# board.net
KiCad netlist of a schematic drawn in EAGLE
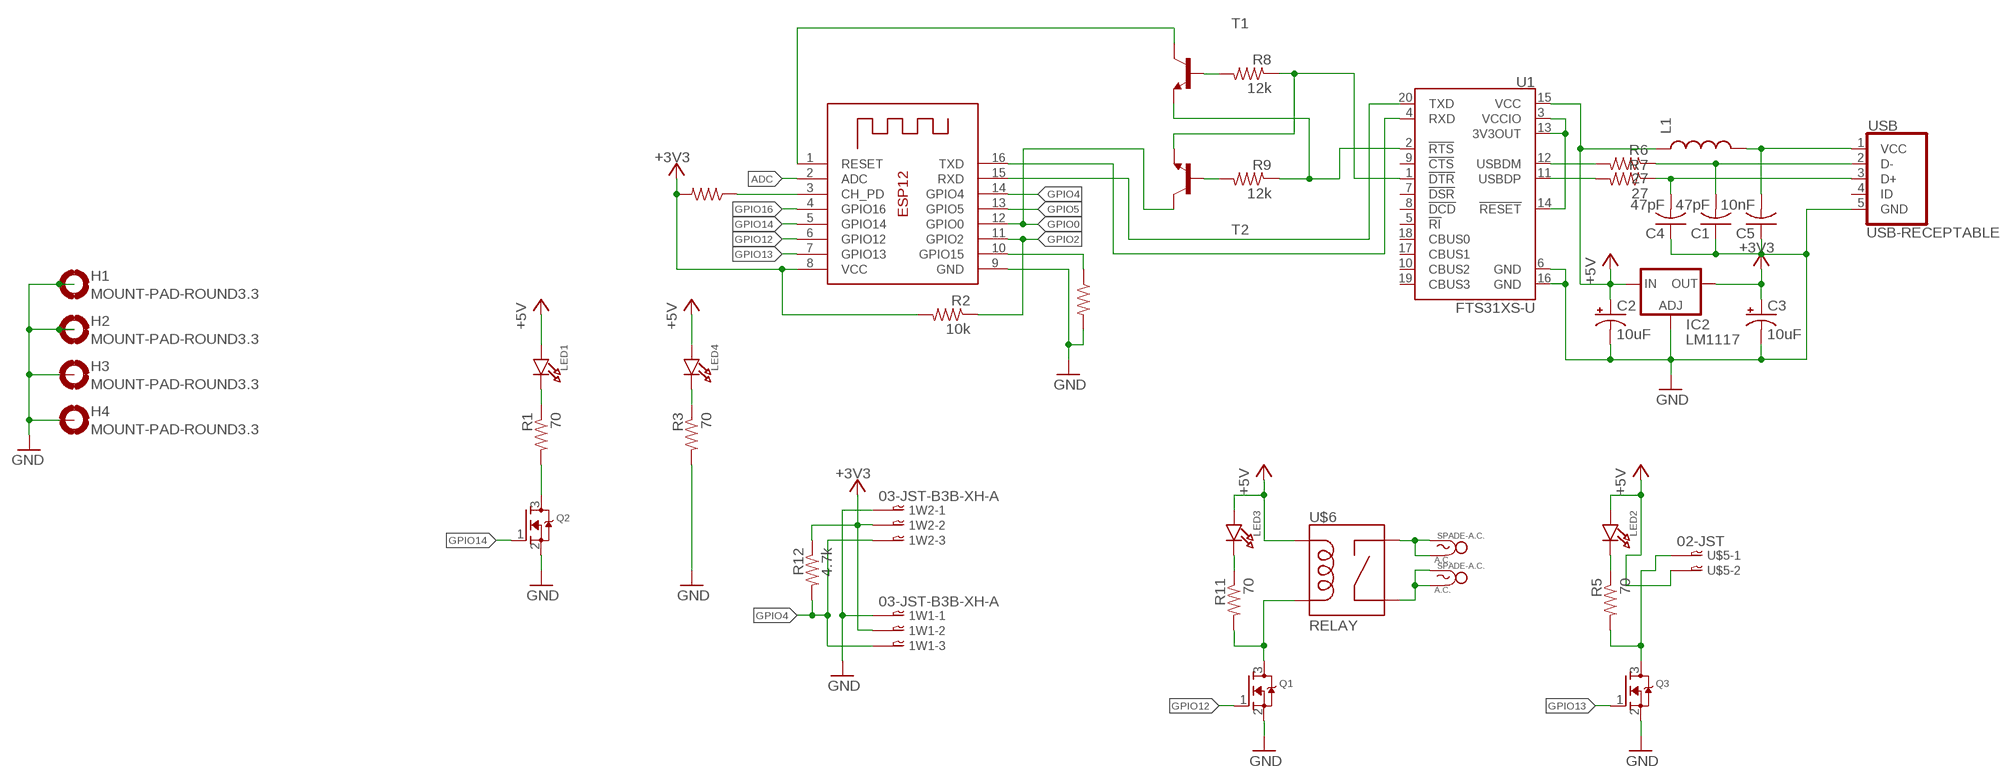
[diagram p0: schematic, sheet 1]

(export (version "E")
  (design (tool "Eeschema 10.0.6"))
  (components
    (comp (ref "1W1")
      (value "03-JST-B3B-XH-A")
      (footprint "eagle-import:B3B-XH")
      (libsource (lib "eagle-import") (part "03-JST-B3B-XH-A"))
    )
    (comp (ref "1W2")
      (value "03-JST-B3B-XH-A")
      (footprint "eagle-import:B3B-XH")
      (libsource (lib "eagle-import") (part "03-JST-B3B-XH-A"))
    )
    (comp (ref "C1")
      (value "47pF")
      (footprint "eagle-import:C0603")
      (libsource (lib "eagle-import") (part "C-USC0603"))
    )
    (comp (ref "C2")
      (value "10uF")
      (footprint "eagle-import:153CLV-0405")
      (libsource (lib "eagle-import") (part "CPOL-US153CLV-0405"))
    )
    (comp (ref "C3")
      (value "10uF")
      (footprint "eagle-import:153CLV-0405")
      (libsource (lib "eagle-import") (part "CPOL-US153CLV-0405"))
    )
    (comp (ref "C4")
      (value "47pF")
      (footprint "eagle-import:C0603")
      (libsource (lib "eagle-import") (part "C-USC0603"))
    )
    (comp (ref "C5")
      (value "10nF")
      (footprint "eagle-import:C0603")
      (libsource (lib "eagle-import") (part "C-USC0603"))
    )
    (comp (ref "H1")
      (value "MOUNT-PAD-ROUND3.3")
      (footprint "eagle-import:3,3-PAD")
      (libsource (lib "eagle-import") (part "MOUNT-PAD-ROUND3.3"))
    )
    (comp (ref "H2")
      (value "MOUNT-PAD-ROUND3.3")
      (footprint "eagle-import:3,3-PAD")
      (libsource (lib "eagle-import") (part "MOUNT-PAD-ROUND3.3"))
    )
    (comp (ref "H3")
      (value "MOUNT-PAD-ROUND3.3")
      (footprint "eagle-import:3,3-PAD")
      (libsource (lib "eagle-import") (part "MOUNT-PAD-ROUND3.3"))
    )
    (comp (ref "H4")
      (value "MOUNT-PAD-ROUND3.3")
      (footprint "eagle-import:3,3-PAD")
      (libsource (lib "eagle-import") (part "MOUNT-PAD-ROUND3.3"))
    )
    (comp (ref "IC2")
      (value "LM1117")
      (footprint "eagle-import:DPACK")
      (libsource (lib "eagle-import") (part "LD117A?DT-TR"))
    )
    (comp (ref "L1")
      (value "INDUCTOR0805")
      (footprint "eagle-import:0805")
      (libsource (lib "eagle-import") (part "INDUCTOR0805"))
    )
    (comp (ref "LED1")
      (value "LED0805")
      (footprint "eagle-import:CHIPLED_0805")
      (libsource (lib "eagle-import") (part "LED0805"))
    )
    (comp (ref "LED2")
      (value "LED0805")
      (footprint "eagle-import:CHIPLED_0805")
      (libsource (lib "eagle-import") (part "LED0805"))
    )
    (comp (ref "LED3")
      (value "LED0805")
      (footprint "eagle-import:CHIPLED_0805")
      (libsource (lib "eagle-import") (part "LED0805"))
    )
    (comp (ref "LED4")
      (value "LED0805")
      (footprint "eagle-import:CHIPLED_0805")
      (libsource (lib "eagle-import") (part "LED0805"))
    )
    (comp (ref "Q1")
      (value "MOSFET-NREFLOW")
      (footprint "eagle-import:SOT23")
      (libsource (lib "eagle-import") (part "MOSFET-NREFLOW"))
    )
    (comp (ref "Q2")
      (value "MOSFET-NREFLOW")
      (footprint "eagle-import:SOT23")
      (libsource (lib "eagle-import") (part "MOSFET-NREFLOW"))
    )
    (comp (ref "Q3")
      (value "MOSFET-NREFLOW")
      (footprint "eagle-import:SOT23")
      (libsource (lib "eagle-import") (part "MOSFET-NREFLOW"))
    )
    (comp (ref "R1")
      (value "70")
      (footprint "eagle-import:R0603")
      (libsource (lib "eagle-import") (part "R-US_R0603"))
    )
    (comp (ref "R2")
      (value "10k")
      (footprint "eagle-import:R0603")
      (libsource (lib "eagle-import") (part "R-US_R0603"))
    )
    (comp (ref "R3")
      (value "70")
      (footprint "eagle-import:R0603")
      (libsource (lib "eagle-import") (part "R-US_R0603"))
    )
    (comp (ref "R4")
      (value "10k")
      (footprint "eagle-import:R0603")
      (libsource (lib "eagle-import") (part "R-US_R0603"))
    )
    (comp (ref "R5")
      (value "70")
      (footprint "eagle-import:R0603")
      (libsource (lib "eagle-import") (part "R-US_R0603"))
    )
    (comp (ref "R6")
      (value "27")
      (footprint "eagle-import:R0603")
      (libsource (lib "eagle-import") (part "R-US_R0603"))
    )
    (comp (ref "R7")
      (value "27")
      (footprint "eagle-import:R0603")
      (libsource (lib "eagle-import") (part "R-US_R0603"))
    )
    (comp (ref "R8")
      (value "12k")
      (footprint "eagle-import:R0603")
      (libsource (lib "eagle-import") (part "R-US_R0603"))
    )
    (comp (ref "R9")
      (value "12k")
      (footprint "eagle-import:R0603")
      (libsource (lib "eagle-import") (part "R-US_R0603"))
    )
    (comp (ref "R10")
      (value "10k")
      (footprint "eagle-import:R0603")
      (libsource (lib "eagle-import") (part "R-US_R0603"))
    )
    (comp (ref "R11")
      (value "70")
      (footprint "eagle-import:R0603")
      (libsource (lib "eagle-import") (part "R-US_R0603"))
    )
    (comp (ref "R12")
      (value "4.7k")
      (footprint "eagle-import:R0603")
      (libsource (lib "eagle-import") (part "R-US_R0603"))
    )
    (comp (ref "T1")
      (value "MMBT918LT1-NPN-SOT23-BEC")
      (footprint "eagle-import:SOT23-BEC")
      (libsource (lib "eagle-import") (part "-NPN-SOT23-BECMMBT918LT1"))
    )
    (comp (ref "T2")
      (value "MMBT918LT1-NPN-SOT23-BEC")
      (footprint "eagle-import:SOT23-BEC")
      (libsource (lib "eagle-import") (part "-NPN-SOT23-BECMMBT918LT1"))
    )
    (comp (ref "U$1")
      (value "SPADE-A.C.")
      (footprint "eagle-import:SPADE-A.C.")
      (libsource (lib "eagle-import") (part "SPADE-A.C."))
    )
    (comp (ref "U$2")
      (value "SPADE-A.C.")
      (footprint "eagle-import:SPADE-A.C.")
      (libsource (lib "eagle-import") (part "SPADE-A.C."))
    )
    (comp (ref "U$5")
      (value "02-JST")
      (footprint "eagle-import:B2B-XH")
      (libsource (lib "eagle-import") (part "02-JST"))
    )
    (comp (ref "U$6")
      (value "RELAY")
      (footprint "eagle-import:RELAY-G5NB")
      (libsource (lib "eagle-import") (part "RELAY"))
    )
    (comp (ref "U1")
      (value "FTS31XS-U")
      (footprint "eagle-import:SSOP20_L")
      (libsource (lib "eagle-import") (part "FT231XS"))
    )
    (comp (ref "USB")
      (value "USB-RECEPTABLE")
      (footprint "eagle-import:FCI-10103594-0001LF")
      (libsource (lib "eagle-import") (part "USB-RECEPTABLE"))
    )
    (comp (ref "X1")
      (value "ESP-12")
      (footprint "eagle-import:ESP-12")
      (libsource (lib "eagle-import") (part "ESP-12"))
    )
  )
  (nets
    (net (code "1") (name "+3V3") (class "Default")
      (node (ref "1W1") (pin "P$2") (pinfunction "1_P$2") (pintype "passive"))
      (node (ref "1W2") (pin "P$2") (pinfunction "1_P$2") (pintype "passive"))
      (node (ref "C3") (pin "+") (pinfunction "+_+") (pintype "passive"))
      (node (ref "IC2") (pin "4") (pinfunction "OUT_4") (pintype "passive"))
      (node (ref "R12") (pin "1") (pinfunction "1_1") (pintype "passive"))
      (node (ref "R2") (pin "2") (pinfunction "2_2") (pintype "passive"))
      (node (ref "R4") (pin "2") (pinfunction "2_2") (pintype "passive"))
      (node (ref "X1") (pin "8") (pinfunction "VCC_8") (pintype "power_in"))
    )
    (net (code "2") (name "+5V") (class "Default")
      (node (ref "C2") (pin "+") (pinfunction "+_+") (pintype "passive"))
      (node (ref "IC2") (pin "3") (pinfunction "IN_3") (pintype "input"))
      (node (ref "L1") (pin "1") (pinfunction "1_1") (pintype "passive"))
      (node (ref "LED1") (pin "A") (pinfunction "A_A") (pintype "passive"))
      (node (ref "LED2") (pin "A") (pinfunction "A_A") (pintype "passive"))
      (node (ref "LED3") (pin "A") (pinfunction "A_A") (pintype "passive"))
      (node (ref "LED4") (pin "A") (pinfunction "A_A") (pintype "passive"))
      (node (ref "U$5") (pin "P$2") (pinfunction "1_P$2") (pintype "passive"))
      (node (ref "U$6") (pin "1") (pinfunction "COIL1_1") (pintype "bidirectional"))
      (node (ref "U1") (pin "15") (pinfunction "VCC_15") (pintype "bidirectional"))
    )
    (net (code "3") (name "ADC") (class "Default")
      (node (ref "X1") (pin "2") (pinfunction "ADC_2") (pintype "passive"))
    )
    (net (code "4") (name "GND") (class "Default")
      (node (ref "1W1") (pin "P$1") (pinfunction "1_P$1") (pintype "passive"))
      (node (ref "1W2") (pin "P$1") (pinfunction "1_P$1") (pintype "passive"))
      (node (ref "C1") (pin "1") (pinfunction "1_1") (pintype "passive"))
      (node (ref "C2") (pin "-") (pinfunction "-_-") (pintype "passive"))
      (node (ref "C3") (pin "-") (pinfunction "-_-") (pintype "passive"))
      (node (ref "C4") (pin "1") (pinfunction "1_1") (pintype "passive"))
      (node (ref "C5") (pin "1") (pinfunction "1_1") (pintype "passive"))
      (node (ref "H1") (pin "B3,3") (pinfunction "MOUNT_B3,3") (pintype "passive"))
      (node (ref "H2") (pin "B3,3") (pinfunction "MOUNT_B3,3") (pintype "passive"))
      (node (ref "H3") (pin "B3,3") (pinfunction "MOUNT_B3,3") (pintype "passive"))
      (node (ref "H4") (pin "B3,3") (pinfunction "MOUNT_B3,3") (pintype "passive"))
      (node (ref "IC2") (pin "1") (pinfunction "ADJ_1") (pintype "input"))
      (node (ref "Q1") (pin "2") (pinfunction "S_2") (pintype "bidirectional"))
      (node (ref "Q2") (pin "2") (pinfunction "S_2") (pintype "bidirectional"))
      (node (ref "Q3") (pin "2") (pinfunction "S_2") (pintype "bidirectional"))
      (node (ref "R10") (pin "2") (pinfunction "2_2") (pintype "passive"))
      (node (ref "R3") (pin "2") (pinfunction "2_2") (pintype "passive"))
      (node (ref "U1") (pin "16") (pinfunction "GND_16") (pintype "bidirectional"))
      (node (ref "U1") (pin "6") (pinfunction "GND_6") (pintype "bidirectional"))
      (node (ref "USB") (pin "5") (pinfunction "GND_5") (pintype "bidirectional"))
      (node (ref "X1") (pin "9") (pinfunction "GND_9") (pintype "power_in"))
    )
    (net (code "5") (name "GPIO0") (class "Default")
      (node (ref "T2") (pin "C") (pinfunction "C_C") (pintype "passive"))
      (node (ref "X1") (pin "12") (pinfunction "GPIO0_12") (pintype "bidirectional"))
    )
    (net (code "6") (name "GPIO2") (class "Default")
      (node (ref "R2") (pin "1") (pinfunction "1_1") (pintype "passive"))
      (node (ref "X1") (pin "11") (pinfunction "GPIO2_11") (pintype "bidirectional"))
    )
    (net (code "7") (name "GPIO4") (class "Default")
      (node (ref "1W1") (pin "P$3") (pinfunction "1_P$3") (pintype "passive"))
      (node (ref "1W2") (pin "P$3") (pinfunction "1_P$3") (pintype "passive"))
      (node (ref "R12") (pin "2") (pinfunction "2_2") (pintype "passive"))
      (node (ref "X1") (pin "14") (pinfunction "GPIO4_14") (pintype "bidirectional"))
    )
    (net (code "8") (name "GPIO5") (class "Default")
      (node (ref "X1") (pin "13") (pinfunction "GPIO5_13") (pintype "bidirectional"))
    )
    (net (code "9") (name "GPIO12") (class "Default")
      (node (ref "Q1") (pin "1") (pinfunction "G_1") (pintype "bidirectional"))
      (node (ref "X1") (pin "6") (pinfunction "GPIO12_6") (pintype "bidirectional"))
    )
    (net (code "10") (name "GPIO13") (class "Default")
      (node (ref "Q3") (pin "1") (pinfunction "G_1") (pintype "bidirectional"))
      (node (ref "X1") (pin "7") (pinfunction "GPIO13_7") (pintype "bidirectional"))
    )
    (net (code "11") (name "GPIO14") (class "Default")
      (node (ref "Q2") (pin "1") (pinfunction "G_1") (pintype "bidirectional"))
      (node (ref "X1") (pin "5") (pinfunction "GPIO14_5") (pintype "bidirectional"))
    )
    (net (code "12") (name "GPIO16") (class "Default")
      (node (ref "X1") (pin "4") (pinfunction "GPIO16_4") (pintype "bidirectional"))
    )
    (net (code "13") (name "Net-(LED1-PadC)") (class "Default")
      (node (ref "LED1") (pin "C") (pinfunction "C_C") (pintype "passive"))
      (node (ref "R1") (pin "1") (pinfunction "1_1") (pintype "passive"))
    )
    (net (code "14") (name "Net-(LED2-PadC)") (class "Default")
      (node (ref "LED2") (pin "C") (pinfunction "C_C") (pintype "passive"))
      (node (ref "R5") (pin "1") (pinfunction "1_1") (pintype "passive"))
    )
    (net (code "15") (name "Net-(LED3-PadC)") (class "Default")
      (node (ref "LED3") (pin "C") (pinfunction "C_C") (pintype "passive"))
      (node (ref "R11") (pin "1") (pinfunction "1_1") (pintype "passive"))
    )
    (net (code "16") (name "Net-(LED4-PadC)") (class "Default")
      (node (ref "LED4") (pin "C") (pinfunction "C_C") (pintype "passive"))
      (node (ref "R3") (pin "1") (pinfunction "1_1") (pintype "passive"))
    )
    (net (code "17") (name "Net-(Q1-D)") (class "Default")
      (node (ref "Q1") (pin "3") (pinfunction "D_3") (pintype "bidirectional"))
      (node (ref "R11") (pin "2") (pinfunction "2_2") (pintype "passive"))
      (node (ref "U$6") (pin "4") (pinfunction "COIL2_4") (pintype "bidirectional"))
    )
    (net (code "18") (name "Net-(Q2-D)") (class "Default")
      (node (ref "Q2") (pin "3") (pinfunction "D_3") (pintype "bidirectional"))
      (node (ref "R1") (pin "2") (pinfunction "2_2") (pintype "passive"))
    )
    (net (code "19") (name "Net-(Q3-D)") (class "Default")
      (node (ref "Q3") (pin "3") (pinfunction "D_3") (pintype "bidirectional"))
      (node (ref "R5") (pin "2") (pinfunction "2_2") (pintype "passive"))
      (node (ref "U$5") (pin "P$1") (pinfunction "1_P$1") (pintype "passive"))
    )
    (net (code "20") (name "Net-(R8-Pad2)") (class "Default")
      (node (ref "R8") (pin "2") (pinfunction "2_2") (pintype "passive"))
      (node (ref "T1") (pin "B") (pinfunction "B_B") (pintype "passive"))
    )
    (net (code "21") (name "Net-(R9-Pad2)") (class "Default")
      (node (ref "R9") (pin "2") (pinfunction "2_2") (pintype "passive"))
      (node (ref "T2") (pin "B") (pinfunction "B_B") (pintype "passive"))
    )
    (net (code "22") (name "Net-(U$6-MAIN)") (class "Default")
      (node (ref "U$1") (pin "P$1") (pinfunction "P$1_P$1") (pintype "bidirectional"))
      (node (ref "U$1") (pin "P$2") (pinfunction "P$2_P$2") (pintype "bidirectional"))
      (node (ref "U$6") (pin "2") (pinfunction "MAIN_2") (pintype "bidirectional"))
    )
    (net (code "23") (name "Net-(U$6-NO)") (class "Default")
      (node (ref "U$2") (pin "P$1") (pinfunction "P$1_P$1") (pintype "bidirectional"))
      (node (ref "U$2") (pin "P$2") (pinfunction "P$2_P$2") (pintype "bidirectional"))
      (node (ref "U$6") (pin "3") (pinfunction "NO_3") (pintype "bidirectional"))
    )
    (net (code "24") (name "Net-(U1-3V3OUT)") (class "Default")
      (node (ref "U1") (pin "13") (pinfunction "3V3OUT_13") (pintype "bidirectional"))
      (node (ref "U1") (pin "14") (pinfunction "~{RESET}_14") (pintype "bidirectional"))
      (node (ref "U1") (pin "3") (pinfunction "VCCIO_3") (pintype "bidirectional"))
    )
    (net (code "25") (name "Net-(U1-RXD)") (class "Default")
      (node (ref "U1") (pin "4") (pinfunction "RXD_4") (pintype "bidirectional"))
      (node (ref "X1") (pin "16") (pinfunction "TXD_16") (pintype "output"))
    )
    (net (code "26") (name "Net-(U1-TXD)") (class "Default")
      (node (ref "U1") (pin "20") (pinfunction "TXD_20") (pintype "bidirectional"))
      (node (ref "X1") (pin "15") (pinfunction "RXD_15") (pintype "input"))
    )
    (net (code "27") (name "Net-(U1-USBDM)") (class "Default")
      (node (ref "R6") (pin "2") (pinfunction "2_2") (pintype "passive"))
      (node (ref "U1") (pin "12") (pinfunction "USBDM_12") (pintype "bidirectional"))
    )
    (net (code "28") (name "Net-(U1-USBDP)") (class "Default")
      (node (ref "R7") (pin "2") (pinfunction "2_2") (pintype "passive"))
      (node (ref "U1") (pin "11") (pinfunction "USBDP_11") (pintype "bidirectional"))
    )
    (net (code "29") (name "Net-(U1-~{DTR})") (class "Default")
      (node (ref "R8") (pin "1") (pinfunction "1_1") (pintype "passive"))
      (node (ref "T2") (pin "E") (pinfunction "E_E") (pintype "passive"))
      (node (ref "U1") (pin "1") (pinfunction "~{DTR}_1") (pintype "bidirectional"))
    )
    (net (code "30") (name "Net-(U1-~{RTS})") (class "Default")
      (node (ref "R9") (pin "1") (pinfunction "1_1") (pintype "passive"))
      (node (ref "T1") (pin "E") (pinfunction "E_E") (pintype "passive"))
      (node (ref "U1") (pin "2") (pinfunction "~{RTS}_2") (pintype "bidirectional"))
    )
    (net (code "31") (name "Net-(USB-D+)") (class "Default")
      (node (ref "C4") (pin "2") (pinfunction "2_2") (pintype "passive"))
      (node (ref "R7") (pin "1") (pinfunction "1_1") (pintype "passive"))
      (node (ref "USB") (pin "3") (pinfunction "D+_3") (pintype "bidirectional"))
    )
    (net (code "32") (name "Net-(USB-D-)") (class "Default")
      (node (ref "C1") (pin "2") (pinfunction "2_2") (pintype "passive"))
      (node (ref "R6") (pin "1") (pinfunction "1_1") (pintype "passive"))
      (node (ref "USB") (pin "2") (pinfunction "D-_2") (pintype "bidirectional"))
    )
    (net (code "33") (name "Net-(USB-VCC)") (class "Default")
      (node (ref "C5") (pin "2") (pinfunction "2_2") (pintype "passive"))
      (node (ref "L1") (pin "2") (pinfunction "2_2") (pintype "passive"))
      (node (ref "USB") (pin "1") (pinfunction "VCC_1") (pintype "bidirectional"))
    )
    (net (code "34") (name "Net-(X1-CH_PD)") (class "Default")
      (node (ref "R4") (pin "1") (pinfunction "1_1") (pintype "passive"))
      (node (ref "X1") (pin "3") (pinfunction "CH_PD_3") (pintype "input"))
    )
    (net (code "35") (name "Net-(X1-GPIO15)") (class "Default")
      (node (ref "R10") (pin "1") (pinfunction "1_1") (pintype "passive"))
      (node (ref "X1") (pin "10") (pinfunction "GPIO15_10") (pintype "bidirectional"))
    )
    (net (code "36") (name "Net-(X1-RESET)") (class "Default")
      (node (ref "T1") (pin "C") (pinfunction "C_C") (pintype "passive"))
      (node (ref "X1") (pin "1") (pinfunction "RESET_1") (pintype "input"))
    )
    (net (code "37") (name "unconnected-(U1-CBUS0-Pad18)") (class "Default")
      (node (ref "U1") (pin "18") (pinfunction "CBUS0_18") (pintype "bidirectional"))
    )
    (net (code "38") (name "unconnected-(U1-CBUS1-Pad17)") (class "Default")
      (node (ref "U1") (pin "17") (pinfunction "CBUS1_17") (pintype "bidirectional"))
    )
    (net (code "39") (name "unconnected-(U1-CBUS2-Pad10)") (class "Default")
      (node (ref "U1") (pin "10") (pinfunction "CBUS2_10") (pintype "bidirectional"))
    )
    (net (code "40") (name "unconnected-(U1-CBUS3-Pad19)") (class "Default")
      (node (ref "U1") (pin "19") (pinfunction "CBUS3_19") (pintype "bidirectional"))
    )
    (net (code "41") (name "unconnected-(U1-~{CTS}-Pad9)") (class "Default")
      (node (ref "U1") (pin "9") (pinfunction "~{CTS}_9") (pintype "bidirectional"))
    )
    (net (code "42") (name "unconnected-(U1-~{DCD}-Pad8)") (class "Default")
      (node (ref "U1") (pin "8") (pinfunction "~{DCD}_8") (pintype "bidirectional"))
    )
    (net (code "43") (name "unconnected-(U1-~{DSR}-Pad7)") (class "Default")
      (node (ref "U1") (pin "7") (pinfunction "~{DSR}_7") (pintype "bidirectional"))
    )
    (net (code "44") (name "unconnected-(U1-~{RI}-Pad5)") (class "Default")
      (node (ref "U1") (pin "5") (pinfunction "~{RI}_5") (pintype "bidirectional"))
    )
    (net (code "45") (name "unconnected-(USB-ID-Pad4)") (class "Default")
      (node (ref "USB") (pin "4") (pinfunction "ID_4") (pintype "bidirectional"))
    )
  )
)
